# Logic.net
KiCad netlist of a schematic drawn in Altium Designer
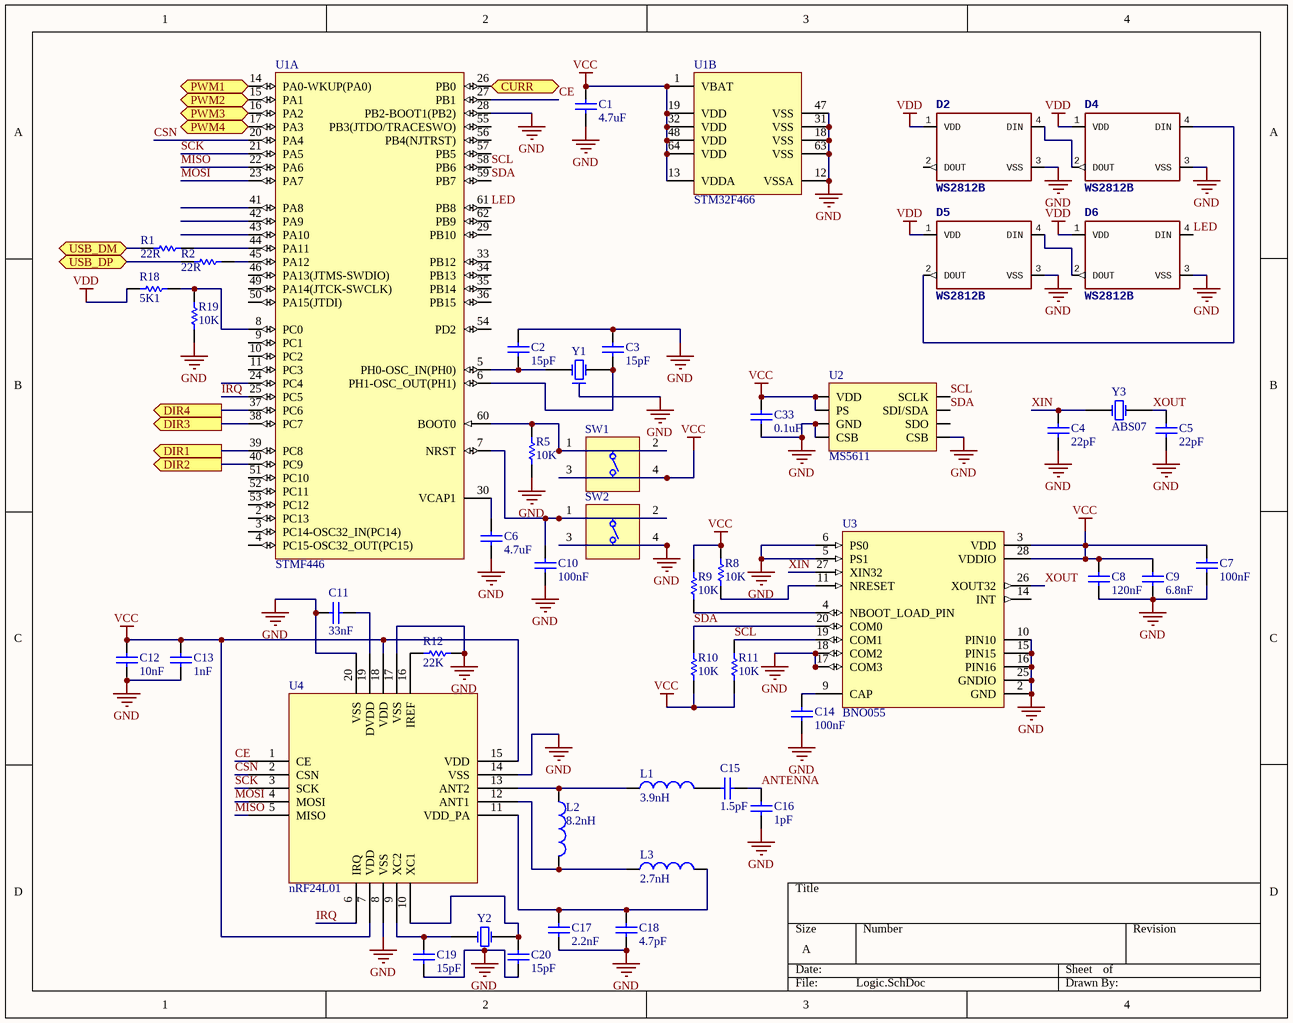
[diagram p0: Logic.SchDoc]

(export (version "E")
  (design (tool "Eeschema 10.0.6"))
  (components
    (comp (ref "C1")
      (value "4.7uF")
      (footprint "CAPC0402(1005)60_L")
      (description "CAP 4.7uF 6.3V ±10% 0402 (1005 Metric) Thickness 0.6mm SMD")
      (fields (field (name "TOLERANCE") "Â±10%"))
      (libsource (lib "Altium Content Vault") (part "CAP"))
    )
    (comp (ref "C2")
      (value "15pF")
      (footprint "CAPC0402(1005)60_M")
      (description "CAP 15pF 25V ±0.25pF 0402 (1005 Metric) Thickness 0.6mm SMD")
      (fields (field (name "TOLERANCE") "Â±0.25pF"))
      (libsource (lib "Altium Content Vault") (part "CMP-1034-00804-1"))
    )
    (comp (ref "C3")
      (value "15pF")
      (footprint "CAPC0402(1005)60_M")
      (description "CAP 15pF 25V ±0.25pF 0402 (1005 Metric) Thickness 0.6mm SMD")
      (fields (field (name "TOLERANCE") "Â±0.25pF"))
      (libsource (lib "Altium Content Vault") (part "CMP-1034-00804-1"))
    )
    (comp (ref "C4")
      (value "22pF")
      (footprint "CAPC0402(1005)60_L")
      (description "CAP 22pF 25V ±10% 0402 (1005 Metric) Thickness 0.6mm SMD")
      (fields (field (name "TOLERANCE") "Â±10%"))
      (libsource (lib "Altium Content Vault") (part "CAP"))
    )
    (comp (ref "C5")
      (value "22pF")
      (footprint "CAPC0402(1005)60_L")
      (description "CAP 22pF 25V ±10% 0402 (1005 Metric) Thickness 0.6mm SMD")
      (fields (field (name "TOLERANCE") "Â±10%"))
      (libsource (lib "Altium Content Vault") (part "CAP"))
    )
    (comp (ref "C6")
      (value "4.7uF")
      (footprint "CAPC0402(1005)60_L")
      (description "CAP 4.7uF 6.3V ±10% 0402 (1005 Metric) Thickness 0.6mm SMD")
      (fields (field (name "TOLERANCE") "Â±10%"))
      (libsource (lib "Altium Content Vault") (part "CMP-1034-02136-1"))
    )
    (comp (ref "C7")
      (value "100nF")
      (footprint "CAPC0402(1005)60_M")
      (description "CAP 100nF 6.3V ±5% 0402 (1005 Metric) Thickness 0.6mm SMD")
      (fields (field (name "TOLERANCE") "Â±5%"))
      (libsource (lib "Altium Content Vault") (part "CAP"))
    )
    (comp (ref "C8")
      (value "120nF")
      (footprint "CAPC0402(1005)60_M")
      (description "CAP 100nF 6.3V ±5% 0402 (1005 Metric) Thickness 0.6mm SMD")
      (fields (field (name "TOLERANCE") "Â±5%"))
      (libsource (lib "Altium Content Vault") (part "CAP"))
    )
    (comp (ref "C9")
      (value "6.8nF")
      (footprint "CAPC0402(1005)60_L")
      (description "CAP 6.8nF 6.3V ±5% 0402 (1005 Metric) Thickness 0.6mm SMD")
      (fields (field (name "TOLERANCE") "Â±5%"))
      (libsource (lib "Altium Content Vault") (part "CAP"))
    )
    (comp (ref "C10")
      (value "100nF")
      (footprint "CAPC0402(1005)60_M")
      (description "CAP 100nF 6.3V ±5% 0402 (1005 Metric) Thickness 0.6mm SMD")
      (fields (field (name "TOLERANCE") "Â±5%"))
      (libsource (lib "Altium Content Vault") (part "CAP"))
    )
    (comp (ref "C11")
      (value "33nF")
      (footprint "CAPC0402(1005)60_M")
      (description "CAP 33nF 6.3V ±10% 0402 (1005 Metric) Thickness 0.6mm SMD")
      (fields (field (name "TOLERANCE") "Â±10%"))
      (libsource (lib "Altium Content Vault") (part "CAP"))
    )
    (comp (ref "C12")
      (value "10nF")
      (footprint "CAPC0402(1005)60_M")
      (description "CAP 10nF 6.3V ±5% 0402 (1005 Metric) Thickness 0.6mm SMD")
      (fields (field (name "TOLERANCE") "Â±5%"))
      (libsource (lib "Altium Content Vault") (part "CAP"))
    )
    (comp (ref "C13")
      (value "1nF")
      (footprint "CAPC0402(1005)60_M")
      (description "CAP 1nF 6.3V ±5% 0402 (1005 Metric) Thickness 0.6mm SMD")
      (fields (field (name "TOLERANCE") "Â±5%"))
      (libsource (lib "Altium Content Vault") (part "CAP"))
    )
    (comp (ref "C14")
      (value "100nF")
      (footprint "CAPC0402(1005)60_M")
      (description "CAP 100nF 6.3V ±5% 0402 (1005 Metric) Thickness 0.6mm SMD")
      (fields (field (name "TOLERANCE") "Â±5%"))
      (libsource (lib "Altium Content Vault") (part "CAP"))
    )
    (comp (ref "C15")
      (value "1.5pF")
      (footprint "CAPC0402(1005)60_L")
      (description "CAP 1.5pF 25V ±0.5pF 0402 (1005 Metric) Thickness 0.6mm SMD")
      (fields (field (name "TOLERANCE") "Â±0.5pF"))
      (libsource (lib "Altium Content Vault") (part "CAP"))
    )
    (comp (ref "C16")
      (value "1pF")
      (footprint "CAPC0402(1005)60_M")
      (description "CAP 1pF 25V ±0.5pF 0402 (1005 Metric) Thickness 0.6mm SMD")
      (fields (field (name "TOLERANCE") "Â±0.5pF"))
      (libsource (lib "Altium Content Vault") (part "CAP"))
    )
    (comp (ref "C17")
      (value "2.2nF")
      (footprint "CAPC0402(1005)60_N")
      (description "CAP 2.2nF 6.3V ±5% 0402 (1005 Metric) Thickness 0.6mm SMD")
      (fields (field (name "TOLERANCE") "Â±5%"))
      (libsource (lib "Altium Content Vault") (part "CAP"))
    )
    (comp (ref "C18")
      (value "4.7pF")
      (footprint "CAPC0402(1005)60_M")
      (description "CAP 4.7pF 25V ±0.1pF 0402 (1005 Metric) Thickness 0.6mm SMD")
      (fields (field (name "TOLERANCE") "Â±0.1pF"))
      (libsource (lib "Altium Content Vault") (part "CAP"))
    )
    (comp (ref "C19")
      (value "15pF")
      (footprint "CAPC0402(1005)60_N")
      (description "CAP 15pF 25V ±10% 0402 (1005 Metric) Thickness 0.6mm SMD")
      (fields (field (name "TOLERANCE") "Â±10%"))
      (libsource (lib "Altium Content Vault") (part "CAP"))
    )
    (comp (ref "C20")
      (value "15pF")
      (footprint "CAPC0402(1005)60_N")
      (description "CAP 15pF 25V ±10% 0402 (1005 Metric) Thickness 0.6mm SMD")
      (fields (field (name "TOLERANCE") "Â±10%"))
      (libsource (lib "Altium Content Vault") (part "CMP-1034-00809-1"))
    )
    (comp (ref "C33")
      (value "0.1uF")
      (footprint "CAPC0402(1005)60_M")
      (description "CAP 100nF 6.3V ±5% 0402 (1005 Metric) Thickness 0.6mm SMD")
      (fields (field (name "TOLERANCE") "Â±5%"))
      (libsource (lib "Altium Content Vault") (part "CAP"))
    )
    (comp (ref "D2") (value "WS2812B") (footprint "WS2812B") (libsource (lib "Components") (part "WS2812B")))
    (comp (ref "D4") (value "WS2812B") (footprint "WS2812B") (libsource (lib "Components") (part "WS2812B")))
    (comp (ref "D5") (value "WS2812B") (footprint "WS2812B") (libsource (lib "Components") (part "WS2812B")))
    (comp (ref "D6") (value "WS2812B") (footprint "WS2812B") (libsource (lib "Components") (part "WS2812B")))
    (comp (ref "L1")
      (value "3.9nH")
      (footprint "INDC0402(1005)_N")
      (description "Inductor")
      (fields (field (name "PUBLISHER") "Altium Limited"))
      (libsource (lib "Components") (part "INDC0402"))
    )
    (comp (ref "L2")
      (value "8.2nH")
      (footprint "INDC0402(1005)_N")
      (description "Inductor")
      (fields (field (name "PUBLISHER") "Altium Limited"))
      (libsource (lib "Components") (part "INDC0402"))
    )
    (comp (ref "L3")
      (value "2.7nH")
      (footprint "INDC0402(1005)_N")
      (description "Inductor")
      (fields (field (name "PUBLISHER") "Altium Limited"))
      (libsource (lib "Components") (part "INDC0402"))
    )
    (comp (ref "R1")
      (value "22R")
      (footprint "RESC0402(1005)_M")
      (description "22R 0.063W 5% 0402 (1005 Metric)  SMD")
      (fields (field (name "POWER") "0.063 W") (field (name "TOLERANCE") "5 %"))
      (libsource (lib "Altium Content Vault") (part "RES"))
    )
    (comp (ref "R2")
      (value "22R")
      (footprint "RESC0402(1005)_M")
      (description "22R 0.063W 5% 0402 (1005 Metric)  SMD")
      (fields (field (name "POWER") "0.063 W") (field (name "TOLERANCE") "5 %"))
      (libsource (lib "Altium Content Vault") (part "RES"))
    )
    (comp (ref "R5")
      (value "10K")
      (footprint "RESC0402(1005)_N")
      (description "10K 0.063W 5% 0402 (1005 Metric)  SMD")
      (fields (field (name "TOLERANCE") "5 %") (field (name "POWER") "0.063 W"))
      (libsource (lib "Altium Content Vault") (part "RES"))
    )
    (comp (ref "R8")
      (value "10K")
      (footprint "RESC0402(1005)_N")
      (description "10K 0.063W 5% 0402 (1005 Metric)  SMD")
      (fields (field (name "TOLERANCE") "5 %") (field (name "POWER") "0.063 W"))
      (libsource (lib "Altium Content Vault") (part "RES"))
    )
    (comp (ref "R9")
      (value "10K")
      (footprint "RESC0402(1005)_N")
      (description "10K 0.063W 5% 0402 (1005 Metric)  SMD")
      (fields (field (name "TOLERANCE") "5 %") (field (name "POWER") "0.063 W"))
      (libsource (lib "Altium Content Vault") (part "RES"))
    )
    (comp (ref "R10")
      (value "10K")
      (footprint "RESC0402(1005)_N")
      (description "10K 0.063W 5% 0402 (1005 Metric)  SMD")
      (fields (field (name "TOLERANCE") "5 %") (field (name "POWER") "0.063 W"))
      (libsource (lib "Altium Content Vault") (part "RES"))
    )
    (comp (ref "R11")
      (value "10K")
      (footprint "RESC0402(1005)_N")
      (description "10K 0.063W 5% 0402 (1005 Metric)  SMD")
      (fields (field (name "TOLERANCE") "5 %") (field (name "POWER") "0.063 W"))
      (libsource (lib "Altium Content Vault") (part "RES"))
    )
    (comp (ref "R12")
      (value "22K")
      (footprint "RESC0402(1005)_L")
      (description "22K 0.063W 5% 0402 (1005 Metric)  SMD")
      (fields (field (name "TOLERANCE") "5 %") (field (name "POWER") "0.063 W"))
      (libsource (lib "Altium Content Vault") (part "RES"))
    )
    (comp (ref "R18")
      (value "5K1")
      (footprint "RESC0402(1005)_L")
      (description "5K1 0.063W 5% 0402 (1005 Metric)  SMD")
      (fields (field (name "TOLERANCE") "5 %") (field (name "POWER") "0.063 W"))
      (libsource (lib "Altium Content Vault") (part "RES"))
    )
    (comp (ref "R19")
      (value "10K")
      (footprint "RESC0402(1005)_N")
      (description "10K 0.063W 5% 0402 (1005 Metric)  SMD")
      (fields (field (name "TOLERANCE") "5 %") (field (name "POWER") "0.063 W"))
      (libsource (lib "Altium Content Vault") (part "RES"))
    )
    (comp (ref "SW1")
      (value "~")
      (footprint "SWITCH")
      (description "Switch, SPNO Push Button SMD")
      (fields (field (name "MANUFACTURER") "Diptronics") (field (name "PARTNUMBER") "DTSM-61NT/R"))
      (libsource (lib "altium-import") (part "root_0_DIPT-DTSM-6_"))
    )
    (comp (ref "SW2")
      (value "~")
      (footprint "SWITCH")
      (description "Switch, SPNO Push Button SMD")
      (fields (field (name "MANUFACTURER") "Diptronics") (field (name "PARTNUMBER") "DTSM-61NT/R"))
      (libsource (lib "altium-import") (part "root_0_DIPT-DTSM-6_"))
    )
    (comp (ref "U1")
      (value "STMF446")
      (footprint "STM-LQFP64_N")
      (libsource (lib "Components") (part "MC-ARM-STM32F4X5-SQ64"))
    )
    (comp (ref "U2") (value "MS5611") (footprint "MS5611") (libsource (lib "Components") (part "MS5611")))
    (comp (ref "U3")
      (value "BNO055")
      (footprint "LGA28R50P4X10_380X520X100")
      (libsource (lib "Components") (part "BNO055"))
    )
    (comp (ref "U4") (value "~") (footprint "QFN20") (libsource (lib "Components") (part "NRF24L01+")))
    (comp (ref "Y1")
      (value "~")
      (footprint "ABRA-ABM3B-4_V")
      (libsource (lib "Components") (part "ABRA-ABM3B-4"))
    )
    (comp (ref "Y2")
      (value "~")
      (footprint "ABRA-ABM3B-4_V")
      (libsource (lib "Components") (part "ABRA-ABM3B-4"))
    )
    (comp (ref "Y3") (value "ABS07") (footprint "ABS07") (libsource (lib "Components") (part "ABS07")))
  )
  (nets
    (net (code "1") (name "/ANTENNA") (class "Default")
      (node (ref "C15") (pin "2") (pinfunction "2_2") (pintype "passive"))
      (node (ref "C16") (pin "2") (pinfunction "2_2") (pintype "passive"))
    )
    (net (code "2") (name "/CE") (class "Default")
      (node (ref "U1") (pin "27") (pinfunction "PB1_27") (pintype "bidirectional"))
      (node (ref "U4") (pin "1") (pinfunction "CE_1") (pintype "passive"))
    )
    (net (code "3") (name "/CSN") (class "Default")
      (node (ref "U1") (pin "20") (pinfunction "PA4_20") (pintype "bidirectional"))
      (node (ref "U4") (pin "2") (pinfunction "CSN_2") (pintype "passive"))
    )
    (net (code "4") (name "/CURR") (class "Default")
      (node (ref "U1") (pin "26") (pinfunction "PB0_26") (pintype "bidirectional"))
    )
    (net (code "5") (name "/DIR1") (class "Default")
      (node (ref "U1") (pin "39") (pinfunction "PC8_39") (pintype "bidirectional"))
    )
    (net (code "6") (name "/DIR2") (class "Default")
      (node (ref "U1") (pin "40") (pinfunction "PC9_40") (pintype "bidirectional"))
    )
    (net (code "7") (name "/DIR3") (class "Default")
      (node (ref "U1") (pin "38") (pinfunction "PC7_38") (pintype "bidirectional"))
    )
    (net (code "8") (name "/DIR4") (class "Default")
      (node (ref "U1") (pin "37") (pinfunction "PC6_37") (pintype "bidirectional"))
    )
    (net (code "9") (name "/IRQ") (class "Default")
      (node (ref "U1") (pin "25") (pinfunction "PC5_25") (pintype "bidirectional"))
      (node (ref "U4") (pin "6") (pinfunction "IRQ_6") (pintype "passive"))
    )
    (net (code "10") (name "/LED") (class "Default")
      (node (ref "D6") (pin "4") (pinfunction "DIN_4") (pintype "passive"))
      (node (ref "U1") (pin "61") (pinfunction "PB8_61") (pintype "bidirectional"))
    )
    (net (code "11") (name "/MISO") (class "Default")
      (node (ref "U1") (pin "22") (pinfunction "PA6_22") (pintype "bidirectional"))
      (node (ref "U4") (pin "5") (pinfunction "MISO_5") (pintype "passive"))
    )
    (net (code "12") (name "/MOSI") (class "Default")
      (node (ref "U1") (pin "23") (pinfunction "PA7_23") (pintype "bidirectional"))
      (node (ref "U4") (pin "4") (pinfunction "MOSI_4") (pintype "passive"))
    )
    (net (code "13") (name "/PWM1") (class "Default")
      (node (ref "U1") (pin "14") (pinfunction "PA0-WKUP(PA0)_14") (pintype "bidirectional"))
    )
    (net (code "14") (name "/PWM2") (class "Default")
      (node (ref "U1") (pin "15") (pinfunction "PA1_15") (pintype "bidirectional"))
    )
    (net (code "15") (name "/PWM3") (class "Default")
      (node (ref "U1") (pin "16") (pinfunction "PA2_16") (pintype "bidirectional"))
    )
    (net (code "16") (name "/PWM4") (class "Default")
      (node (ref "U1") (pin "17") (pinfunction "PA3_17") (pintype "bidirectional"))
    )
    (net (code "17") (name "/SCK") (class "Default")
      (node (ref "U1") (pin "21") (pinfunction "PA5_21") (pintype "bidirectional"))
      (node (ref "U4") (pin "3") (pinfunction "SCK_3") (pintype "passive"))
    )
    (net (code "18") (name "/SCL") (class "Default")
      (node (ref "R11") (pin "2") (pinfunction "2_2") (pintype "passive"))
      (node (ref "U1") (pin "58") (pinfunction "PB6_58") (pintype "bidirectional"))
      (node (ref "U2") (pin "8") (pinfunction "SCLK_8") (pintype "passive"))
      (node (ref "U3") (pin "19") (pinfunction "COM1_19") (pintype "bidirectional"))
    )
    (net (code "19") (name "/SDA") (class "Default")
      (node (ref "R10") (pin "2") (pinfunction "2_2") (pintype "passive"))
      (node (ref "U1") (pin "59") (pinfunction "PB7_59") (pintype "bidirectional"))
      (node (ref "U2") (pin "7") (pinfunction "SDI/SDA_7") (pintype "passive"))
      (node (ref "U3") (pin "20") (pinfunction "COM0_20") (pintype "bidirectional"))
    )
    (net (code "20") (name "/USB_DM") (class "Default")
      (node (ref "R1") (pin "1") (pinfunction "1_1") (pintype "passive"))
    )
    (net (code "21") (name "/USB_DP") (class "Default")
      (node (ref "R2") (pin "1") (pinfunction "1_1") (pintype "passive"))
    )
    (net (code "22") (name "/XIN") (class "Default")
      (node (ref "C4") (pin "2") (pinfunction "2_2") (pintype "passive"))
      (node (ref "U3") (pin "27") (pinfunction "XIN32_27") (pintype "input"))
      (node (ref "Y3") (pin "1") (pinfunction "X1_1") (pintype "passive"))
    )
    (net (code "23") (name "/XOUT") (class "Default")
      (node (ref "C5") (pin "2") (pinfunction "2_2") (pintype "passive"))
      (node (ref "U3") (pin "26") (pinfunction "XOUT32_26") (pintype "output"))
      (node (ref "Y3") (pin "2") (pinfunction "X2_2") (pintype "passive"))
    )
    (net (code "24") (name "GND") (class "Default")
      (node (ref "C1") (pin "1") (pinfunction "1_1") (pintype "passive"))
      (node (ref "C10") (pin "1") (pinfunction "1_1") (pintype "passive"))
      (node (ref "C11") (pin "1") (pinfunction "1_1") (pintype "passive"))
      (node (ref "C12") (pin "1") (pinfunction "1_1") (pintype "passive"))
      (node (ref "C13") (pin "1") (pinfunction "1_1") (pintype "passive"))
      (node (ref "C14") (pin "1") (pinfunction "1_1") (pintype "passive"))
      (node (ref "C16") (pin "1") (pinfunction "1_1") (pintype "passive"))
      (node (ref "C17") (pin "1") (pinfunction "1_1") (pintype "passive"))
      (node (ref "C18") (pin "1") (pinfunction "1_1") (pintype "passive"))
      (node (ref "C19") (pin "1") (pinfunction "1_1") (pintype "passive"))
      (node (ref "C2") (pin "2") (pinfunction "2_2") (pintype "passive"))
      (node (ref "C20") (pin "1") (pinfunction "1_1") (pintype "passive"))
      (node (ref "C3") (pin "2") (pinfunction "2_2") (pintype "passive"))
      (node (ref "C33") (pin "1") (pinfunction "1_1") (pintype "passive"))
      (node (ref "C4") (pin "1") (pinfunction "1_1") (pintype "passive"))
      (node (ref "C5") (pin "1") (pinfunction "1_1") (pintype "passive"))
      (node (ref "C6") (pin "1") (pinfunction "1_1") (pintype "passive"))
      (node (ref "C7") (pin "1") (pinfunction "1_1") (pintype "passive"))
      (node (ref "C8") (pin "1") (pinfunction "1_1") (pintype "passive"))
      (node (ref "C9") (pin "1") (pinfunction "1_1") (pintype "passive"))
      (node (ref "D2") (pin "3") (pinfunction "VSS_3") (pintype "power_in"))
      (node (ref "D4") (pin "3") (pinfunction "VSS_3") (pintype "power_in"))
      (node (ref "D5") (pin "3") (pinfunction "VSS_3") (pintype "power_in"))
      (node (ref "D6") (pin "3") (pinfunction "VSS_3") (pintype "power_in"))
      (node (ref "R12") (pin "1") (pinfunction "1_1") (pintype "passive"))
      (node (ref "R19") (pin "1") (pinfunction "1_1") (pintype "passive"))
      (node (ref "R5") (pin "1") (pinfunction "1_1") (pintype "passive"))
      (node (ref "SW2") (pin "3") (pinfunction "T3_3") (pintype "passive"))
      (node (ref "SW2") (pin "4") (pinfunction "T3_4") (pintype "passive"))
      (node (ref "U1") (pin "12") (pinfunction "VSSA_12") (pintype "power_in"))
      (node (ref "U1") (pin "18") (pinfunction "VSS_18") (pintype "power_in"))
      (node (ref "U1") (pin "28") (pinfunction "PB2-BOOT1(PB2)_28") (pintype "bidirectional"))
      (node (ref "U1") (pin "31") (pinfunction "VSS_31") (pintype "power_in"))
      (node (ref "U1") (pin "47") (pinfunction "VSS_47") (pintype "power_in"))
      (node (ref "U1") (pin "63") (pinfunction "VSS_63") (pintype "power_in"))
      (node (ref "U2") (pin "3") (pinfunction "GND_3") (pintype "passive"))
      (node (ref "U2") (pin "4") (pinfunction "CSB_4") (pintype "passive"))
      (node (ref "U2") (pin "5") (pinfunction "CSB_5") (pintype "passive"))
      (node (ref "U3") (pin "10") (pinfunction "PIN10_10") (pintype "power_in"))
      (node (ref "U3") (pin "15") (pinfunction "PIN15_15") (pintype "power_in"))
      (node (ref "U3") (pin "16") (pinfunction "PIN16_16") (pintype "power_in"))
      (node (ref "U3") (pin "17") (pinfunction "COM3_17") (pintype "bidirectional"))
      (node (ref "U3") (pin "18") (pinfunction "COM2_18") (pintype "bidirectional"))
      (node (ref "U3") (pin "2") (pinfunction "GND_2") (pintype "power_in"))
      (node (ref "U3") (pin "25") (pinfunction "GNDIO_25") (pintype "power_in"))
      (node (ref "U3") (pin "5") (pinfunction "PS1_5") (pintype "input"))
      (node (ref "U3") (pin "6") (pinfunction "PS0_6") (pintype "input"))
      (node (ref "U4") (pin "14") (pinfunction "VSS_14") (pintype "passive"))
      (node (ref "U4") (pin "17") (pinfunction "VSS_17") (pintype "passive"))
      (node (ref "U4") (pin "20") (pinfunction "VSS_20") (pintype "passive"))
      (node (ref "U4") (pin "8") (pinfunction "VSS_8") (pintype "passive"))
      (node (ref "Y1") (pin "2") (pinfunction "2_2") (pintype "passive"))
      (node (ref "Y2") (pin "2") (pinfunction "2_2") (pintype "passive"))
    )
    (net (code "25") (name "Net-(C15-Pad1)") (class "Default")
      (node (ref "C15") (pin "1") (pinfunction "1_1") (pintype "passive"))
      (node (ref "L1") (pin "2") (pinfunction "2_2") (pintype "passive"))
    )
    (net (code "26") (name "Net-(D2-DIN)") (class "Default")
      (node (ref "D2") (pin "4") (pinfunction "DIN_4") (pintype "passive"))
      (node (ref "D4") (pin "2") (pinfunction "DOUT_2") (pintype "output"))
    )
    (net (code "27") (name "Net-(D4-DIN)") (class "Default")
      (node (ref "D4") (pin "4") (pinfunction "DIN_4") (pintype "passive"))
      (node (ref "D5") (pin "2") (pinfunction "DOUT_2") (pintype "output"))
    )
    (net (code "28") (name "Net-(D5-DIN)") (class "Default")
      (node (ref "D5") (pin "4") (pinfunction "DIN_4") (pintype "passive"))
      (node (ref "D6") (pin "2") (pinfunction "DOUT_2") (pintype "output"))
    )
    (net (code "29") (name "Net-(SW1-T1)") (class "Default")
      (node (ref "R5") (pin "2") (pinfunction "2_2") (pintype "passive"))
      (node (ref "SW1") (pin "1") (pinfunction "T1_1") (pintype "passive"))
      (node (ref "SW1") (pin "2") (pinfunction "T2_2") (pintype "passive"))
      (node (ref "U1") (pin "60") (pinfunction "BOOT0_60") (pintype "input"))
    )
    (net (code "30") (name "Net-(SW2-T1)") (class "Default")
      (node (ref "C10") (pin "2") (pinfunction "2_2") (pintype "passive"))
      (node (ref "SW2") (pin "1") (pinfunction "T1_1") (pintype "passive"))
      (node (ref "SW2") (pin "2") (pinfunction "T2_2") (pintype "passive"))
      (node (ref "U1") (pin "7") (pinfunction "NRST_7") (pintype "bidirectional"))
    )
    (net (code "31") (name "Net-(U1A-PA11)") (class "Default")
      (node (ref "R1") (pin "2") (pinfunction "2_2") (pintype "passive"))
      (node (ref "U1") (pin "44") (pinfunction "PA11_44") (pintype "bidirectional"))
    )
    (net (code "32") (name "Net-(U1A-PA12)") (class "Default")
      (node (ref "R2") (pin "2") (pinfunction "2_2") (pintype "passive"))
      (node (ref "U1") (pin "45") (pinfunction "PA12_45") (pintype "bidirectional"))
    )
    (net (code "33") (name "Net-(U1A-PC0)") (class "Default")
      (node (ref "R18") (pin "1") (pinfunction "1_1") (pintype "passive"))
      (node (ref "R19") (pin "2") (pinfunction "2_2") (pintype "passive"))
      (node (ref "U1") (pin "8") (pinfunction "PC0_8") (pintype "bidirectional"))
    )
    (net (code "34") (name "Net-(U1A-PH0-OSC_IN(PH0))") (class "Default")
      (node (ref "C2") (pin "1") (pinfunction "1_1") (pintype "passive"))
      (node (ref "U1") (pin "5") (pinfunction "PH0-OSC_IN(PH0)_5") (pintype "bidirectional"))
      (node (ref "Y1") (pin "1") (pinfunction "X1_1") (pintype "passive"))
    )
    (net (code "35") (name "Net-(U1A-PH1-OSC_OUT(PH1))") (class "Default")
      (node (ref "C3") (pin "1") (pinfunction "1_1") (pintype "passive"))
      (node (ref "U1") (pin "6") (pinfunction "PH1-OSC_OUT(PH1)_6") (pintype "bidirectional"))
      (node (ref "Y1") (pin "3") (pinfunction "X2_3") (pintype "passive"))
    )
    (net (code "36") (name "Net-(U1A-VCAP1)") (class "Default")
      (node (ref "C6") (pin "2") (pinfunction "2_2") (pintype "passive"))
      (node (ref "U1") (pin "30") (pinfunction "VCAP1_30") (pintype "power_in"))
    )
    (net (code "37") (name "Net-(U3-CAP)") (class "Default")
      (node (ref "C14") (pin "2") (pinfunction "2_2") (pintype "passive"))
      (node (ref "U3") (pin "9") (pinfunction "CAP_9") (pintype "passive"))
    )
    (net (code "38") (name "Net-(U3-NBOOT_LOAD_PIN)") (class "Default")
      (node (ref "R9") (pin "1") (pinfunction "1_1") (pintype "passive"))
      (node (ref "U3") (pin "4") (pinfunction "NBOOT_LOAD_PIN_4") (pintype "bidirectional"))
    )
    (net (code "39") (name "Net-(U3-NRESET)") (class "Default")
      (node (ref "R8") (pin "1") (pinfunction "1_1") (pintype "passive"))
      (node (ref "U3") (pin "11") (pinfunction "NRESET_11") (pintype "input"))
    )
    (net (code "40") (name "Net-(U4-ANT1)") (class "Default")
      (node (ref "L2") (pin "2") (pinfunction "2_2") (pintype "passive"))
      (node (ref "L3") (pin "1") (pinfunction "1_1") (pintype "passive"))
      (node (ref "U4") (pin "12") (pinfunction "ANT1_12") (pintype "passive"))
    )
    (net (code "41") (name "Net-(U4-ANT2)") (class "Default")
      (node (ref "L1") (pin "1") (pinfunction "1_1") (pintype "passive"))
      (node (ref "L2") (pin "1") (pinfunction "1_1") (pintype "passive"))
      (node (ref "U4") (pin "13") (pinfunction "ANT2_13") (pintype "passive"))
    )
    (net (code "42") (name "Net-(U4-DVDD)") (class "Default")
      (node (ref "C11") (pin "2") (pinfunction "2_2") (pintype "passive"))
      (node (ref "U4") (pin "19") (pinfunction "DVDD_19") (pintype "passive"))
    )
    (net (code "43") (name "Net-(U4-IREF)") (class "Default")
      (node (ref "R12") (pin "2") (pinfunction "2_2") (pintype "passive"))
      (node (ref "U4") (pin "16") (pinfunction "IREF_16") (pintype "passive"))
    )
    (net (code "44") (name "Net-(U4-VDD_PA)") (class "Default")
      (node (ref "C17") (pin "2") (pinfunction "2_2") (pintype "passive"))
      (node (ref "C18") (pin "2") (pinfunction "2_2") (pintype "passive"))
      (node (ref "L3") (pin "2") (pinfunction "2_2") (pintype "passive"))
      (node (ref "U4") (pin "11") (pinfunction "VDD_PA_11") (pintype "passive"))
    )
    (net (code "45") (name "Net-(U4-XC1)") (class "Default")
      (node (ref "C20") (pin "2") (pinfunction "2_2") (pintype "passive"))
      (node (ref "U4") (pin "10") (pinfunction "XC1_10") (pintype "passive"))
      (node (ref "Y2") (pin "3") (pinfunction "X2_3") (pintype "passive"))
    )
    (net (code "46") (name "Net-(U4-XC2)") (class "Default")
      (node (ref "C19") (pin "2") (pinfunction "2_2") (pintype "passive"))
      (node (ref "U4") (pin "9") (pinfunction "XC2_9") (pintype "passive"))
      (node (ref "Y2") (pin "1") (pinfunction "X1_1") (pintype "passive"))
    )
    (net (code "47") (name "VCC") (class "Default")
      (node (ref "C1") (pin "2") (pinfunction "2_2") (pintype "passive"))
      (node (ref "C12") (pin "2") (pinfunction "2_2") (pintype "passive"))
      (node (ref "C13") (pin "2") (pinfunction "2_2") (pintype "passive"))
      (node (ref "C33") (pin "2") (pinfunction "2_2") (pintype "passive"))
      (node (ref "C7") (pin "2") (pinfunction "2_2") (pintype "passive"))
      (node (ref "C8") (pin "2") (pinfunction "2_2") (pintype "passive"))
      (node (ref "C9") (pin "2") (pinfunction "2_2") (pintype "passive"))
      (node (ref "R10") (pin "1") (pinfunction "1_1") (pintype "passive"))
      (node (ref "R11") (pin "1") (pinfunction "1_1") (pintype "passive"))
      (node (ref "R8") (pin "2") (pinfunction "2_2") (pintype "passive"))
      (node (ref "R9") (pin "2") (pinfunction "2_2") (pintype "passive"))
      (node (ref "SW1") (pin "3") (pinfunction "T3_3") (pintype "passive"))
      (node (ref "SW1") (pin "4") (pinfunction "T3_4") (pintype "passive"))
      (node (ref "U1") (pin "1") (pinfunction "VBAT_1") (pintype "power_in"))
      (node (ref "U1") (pin "13") (pinfunction "VDDA_13") (pintype "power_in"))
      (node (ref "U1") (pin "19") (pinfunction "VDD_19") (pintype "power_in"))
      (node (ref "U1") (pin "32") (pinfunction "VDD_32") (pintype "power_in"))
      (node (ref "U1") (pin "48") (pinfunction "VDD_48") (pintype "power_in"))
      (node (ref "U1") (pin "64") (pinfunction "VDD_64") (pintype "power_in"))
      (node (ref "U2") (pin "1") (pinfunction "VDD_1") (pintype "passive"))
      (node (ref "U2") (pin "2") (pinfunction "PS_2") (pintype "passive"))
      (node (ref "U3") (pin "28") (pinfunction "VDDIO_28") (pintype "power_in"))
      (node (ref "U3") (pin "3") (pinfunction "VDD_3") (pintype "power_in"))
      (node (ref "U4") (pin "15") (pinfunction "VDD_15") (pintype "passive"))
      (node (ref "U4") (pin "18") (pinfunction "VDD_18") (pintype "passive"))
      (node (ref "U4") (pin "7") (pinfunction "VDD_7") (pintype "passive"))
    )
    (net (code "48") (name "VDD") (class "Default")
      (node (ref "D2") (pin "1") (pinfunction "VDD_1") (pintype "power_in"))
      (node (ref "D4") (pin "1") (pinfunction "VDD_1") (pintype "power_in"))
      (node (ref "D5") (pin "1") (pinfunction "VDD_1") (pintype "power_in"))
      (node (ref "D6") (pin "1") (pinfunction "VDD_1") (pintype "power_in"))
      (node (ref "R18") (pin "2") (pinfunction "2_2") (pintype "passive"))
    )
    (net (code "49") (name "unconnected-(D2-DOUT-Pad2)") (class "Default")
      (node (ref "D2") (pin "2") (pinfunction "DOUT_2") (pintype "output"))
    )
    (net (code "50") (name "unconnected-(U1A-PA8-Pad41)") (class "Default")
      (node (ref "U1") (pin "41") (pinfunction "PA8_41") (pintype "bidirectional"))
    )
    (net (code "51") (name "unconnected-(U1A-PA9-Pad42)") (class "Default")
      (node (ref "U1") (pin "42") (pinfunction "PA9_42") (pintype "bidirectional"))
    )
    (net (code "52") (name "unconnected-(U1A-PA10-Pad43)") (class "Default")
      (node (ref "U1") (pin "43") (pinfunction "PA10_43") (pintype "bidirectional"))
    )
    (net (code "53") (name "unconnected-(U1A-PA13(JTMS-SWDIO)-Pad46)") (class "Default")
      (node (ref "U1") (pin "46") (pinfunction "PA13(JTMS-SWDIO)_46") (pintype "bidirectional"))
    )
    (net (code "54") (name "unconnected-(U1A-PA14(JTCK-SWCLK)-Pad49)") (class "Default")
      (node (ref "U1") (pin "49") (pinfunction "PA14(JTCK-SWCLK)_49") (pintype "bidirectional"))
    )
    (net (code "55") (name "unconnected-(U1A-PA15(JTDI)-Pad50)") (class "Default")
      (node (ref "U1") (pin "50") (pinfunction "PA15(JTDI)_50") (pintype "bidirectional"))
    )
    (net (code "56") (name "unconnected-(U1A-PB3(JTDO{slash}TRACESWO)-Pad55)") (class "Default")
      (node (ref "U1") (pin "55") (pinfunction "PB3(JTDO/TRACESWO)_55") (pintype "bidirectional"))
    )
    (net (code "57") (name "unconnected-(U1A-PB4(NJTRST)-Pad56)") (class "Default")
      (node (ref "U1") (pin "56") (pinfunction "PB4(NJTRST)_56") (pintype "bidirectional"))
    )
    (net (code "58") (name "unconnected-(U1A-PB5-Pad57)") (class "Default")
      (node (ref "U1") (pin "57") (pinfunction "PB5_57") (pintype "bidirectional"))
    )
    (net (code "59") (name "unconnected-(U1A-PB9-Pad62)") (class "Default")
      (node (ref "U1") (pin "62") (pinfunction "PB9_62") (pintype "bidirectional"))
    )
    (net (code "60") (name "unconnected-(U1A-PB10-Pad29)") (class "Default")
      (node (ref "U1") (pin "29") (pinfunction "PB10_29") (pintype "bidirectional"))
    )
    (net (code "61") (name "unconnected-(U1A-PB12-Pad33)") (class "Default")
      (node (ref "U1") (pin "33") (pinfunction "PB12_33") (pintype "bidirectional"))
    )
    (net (code "62") (name "unconnected-(U1A-PB13-Pad34)") (class "Default")
      (node (ref "U1") (pin "34") (pinfunction "PB13_34") (pintype "bidirectional"))
    )
    (net (code "63") (name "unconnected-(U1A-PB14-Pad35)") (class "Default")
      (node (ref "U1") (pin "35") (pinfunction "PB14_35") (pintype "bidirectional"))
    )
    (net (code "64") (name "unconnected-(U1A-PB15-Pad36)") (class "Default")
      (node (ref "U1") (pin "36") (pinfunction "PB15_36") (pintype "bidirectional"))
    )
    (net (code "65") (name "unconnected-(U1A-PC1-Pad9)") (class "Default")
      (node (ref "U1") (pin "9") (pinfunction "PC1_9") (pintype "bidirectional"))
    )
    (net (code "66") (name "unconnected-(U1A-PC2-Pad10)") (class "Default")
      (node (ref "U1") (pin "10") (pinfunction "PC2_10") (pintype "bidirectional"))
    )
    (net (code "67") (name "unconnected-(U1A-PC3-Pad11)") (class "Default")
      (node (ref "U1") (pin "11") (pinfunction "PC3_11") (pintype "bidirectional"))
    )
    (net (code "68") (name "unconnected-(U1A-PC4-Pad24)") (class "Default")
      (node (ref "U1") (pin "24") (pinfunction "PC4_24") (pintype "bidirectional"))
    )
    (net (code "69") (name "unconnected-(U1A-PC10-Pad51)") (class "Default")
      (node (ref "U1") (pin "51") (pinfunction "PC10_51") (pintype "bidirectional"))
    )
    (net (code "70") (name "unconnected-(U1A-PC11-Pad52)") (class "Default")
      (node (ref "U1") (pin "52") (pinfunction "PC11_52") (pintype "bidirectional"))
    )
    (net (code "71") (name "unconnected-(U1A-PC12-Pad53)") (class "Default")
      (node (ref "U1") (pin "53") (pinfunction "PC12_53") (pintype "bidirectional"))
    )
    (net (code "72") (name "unconnected-(U1A-PC13-Pad2)") (class "Default")
      (node (ref "U1") (pin "2") (pinfunction "PC13_2") (pintype "bidirectional"))
    )
    (net (code "73") (name "unconnected-(U1A-PC14-OSC32_IN(PC14)-Pad3)") (class "Default")
      (node (ref "U1") (pin "3") (pinfunction "PC14-OSC32_IN(PC14)_3") (pintype "bidirectional"))
    )
    (net (code "74") (name "unconnected-(U1A-PC15-OSC32_OUT(PC15)-Pad4)") (class "Default")
      (node (ref "U1") (pin "4") (pinfunction "PC15-OSC32_OUT(PC15)_4") (pintype "bidirectional"))
    )
    (net (code "75") (name "unconnected-(U1A-PD2-Pad54)") (class "Default")
      (node (ref "U1") (pin "54") (pinfunction "PD2_54") (pintype "bidirectional"))
    )
    (net (code "76") (name "unconnected-(U2-SDO-Pad6)") (class "Default")
      (node (ref "U2") (pin "6") (pinfunction "SDO_6") (pintype "passive"))
    )
    (net (code "77") (name "unconnected-(U3-INT-Pad14)") (class "Default")
      (node (ref "U3") (pin "14") (pinfunction "INT_14") (pintype "output"))
    )
  )
)
